# INPUT_AND_OUPUT.net
KiCad netlist of a schematic drawn in Altium Designer
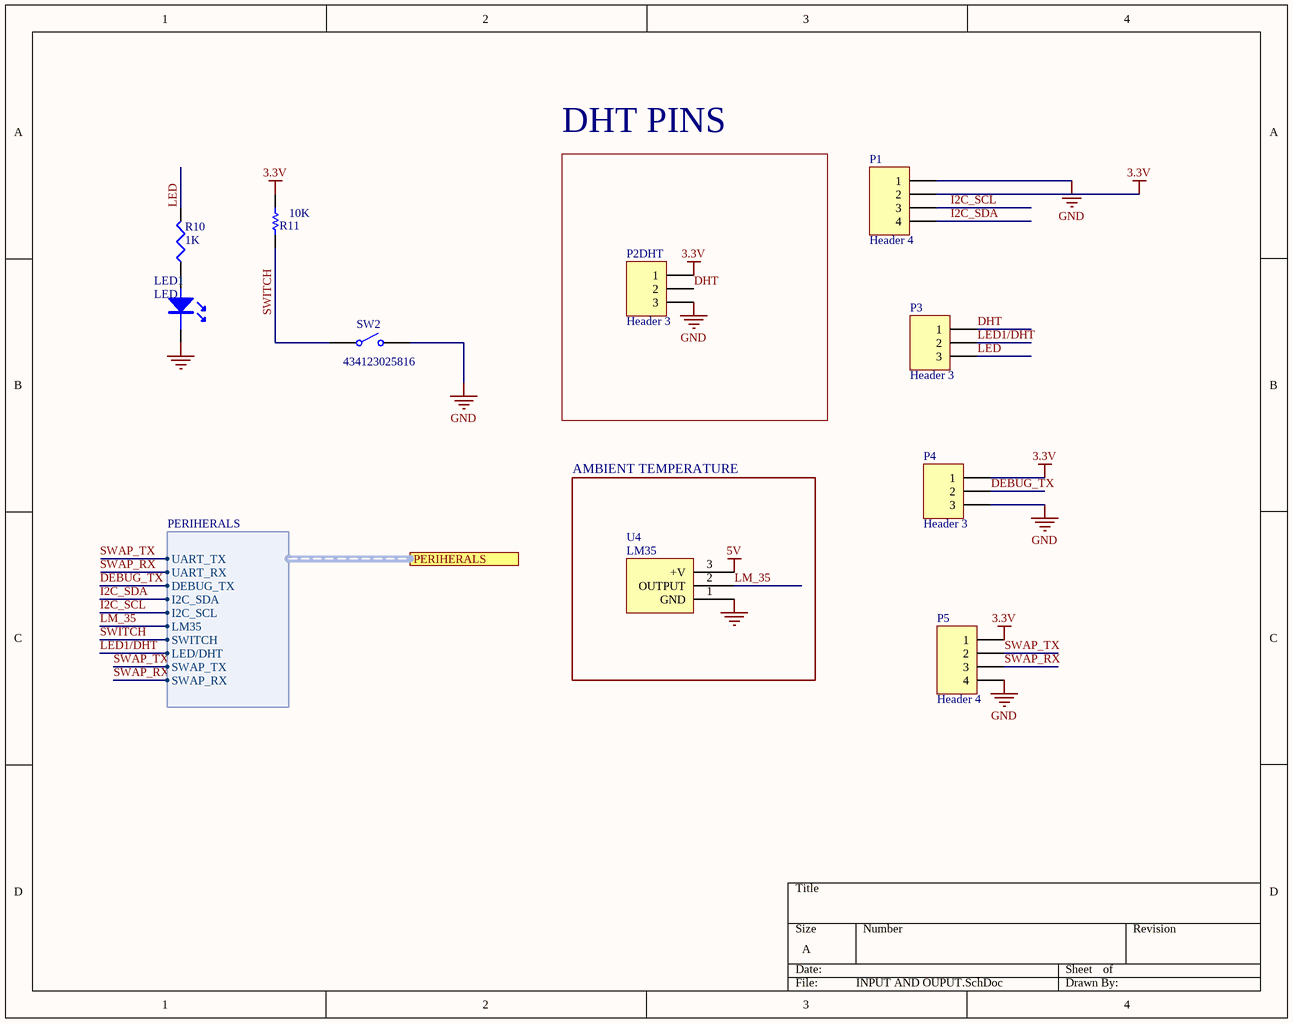
[diagram p0: INPUT AND OUPUT.SchDoc]

(export (version "E")
  (design (tool "Eeschema 10.0.6"))
  (components
    (comp (ref "LED1") (value "LED") (footprint "Type 3mm") (libsource (lib "Devices") (part "LED")))
    (comp (ref "P1")
      (value "Header 4")
      (footprint "HDR1X4")
      (description "Header, 4-Pin")
      (fields (field (name "PUBLISHER") "Altium Limited"))
      (libsource (lib "Miscellaneous Connectors") (part "Header 4"))
    )
    (comp (ref "P2DHT")
      (value "Header 3")
      (footprint "HDR1X3")
      (description "Header, 3-Pin")
      (fields (field (name "PUBLISHER") "Altium Limited"))
      (libsource (lib "Miscellaneous Connectors") (part "Header 3"))
    )
    (comp (ref "P3")
      (value "Header 3")
      (footprint "HDR1X3")
      (description "Header, 3-Pin")
      (fields (field (name "PUBLISHER") "Altium Limited"))
      (libsource (lib "Miscellaneous Connectors") (part "Header 3"))
    )
    (comp (ref "P4")
      (value "Header 3")
      (footprint "HDR1X3")
      (description "Header, 3-Pin")
      (fields (field (name "PUBLISHER") "Altium Limited"))
      (libsource (lib "Miscellaneous Connectors") (part "Header 3"))
    )
    (comp (ref "P5")
      (value "Header 4")
      (footprint "HDR1X4")
      (description "Header, 4-Pin")
      (fields (field (name "PUBLISHER") "Altium Limited"))
      (libsource (lib "Miscellaneous Connectors") (part "Header 4"))
    )
    (comp (ref "R10")
      (value "1K")
      (footprint "RESC0603")
      (description "RESISTOR")
      (libsource (lib "Devices") (part "RES1"))
    )
    (comp (ref "R11")
      (value "10K")
      (footprint "RESC0603")
      (description "2R55 0.125W 1% 0805 (2012 Metric)  SMD")
      (fields (field (name "TOLERANCE") "1 %") (field (name "POWER") "0.125 W"))
      (libsource (lib "Components - 22.01.19 - 11.39") (part "RES"))
    )
    (comp (ref "SW2")
      (value "434123025816")
      (footprint "434123025816")
      (description "WS-TASV J-Bend SMD Tact Switch 6.0X3.8 mm")
      (fields (field (name "MANUFACTURER") "Wuerth Elektronik"))
      (libsource (lib "Altium Content Vault") (part "WE-TACT-SW-2"))
    )
    (comp (ref "U4") (value "LM35") (footprint "TO92S") (libsource (lib "CustomParts") (part "LM35")))
  )
  (nets
    (net (code "2") (name "/DEBUG_TX") (class "Default")
      (node (ref "P4") (pin "2") (pinfunction "2_2") (pintype "passive"))
    )
    (net (code "3") (name "/DHT") (class "Default")
      (node (ref "P2DHT") (pin "2") (pinfunction "2_2") (pintype "passive"))
      (node (ref "P3") (pin "1") (pinfunction "1_1") (pintype "passive"))
    )
    (net (code "4") (name "/I2C_SCL") (class "Default")
      (node (ref "P1") (pin "3") (pinfunction "3_3") (pintype "passive"))
    )
    (net (code "5") (name "/I2C_SDA") (class "Default")
      (node (ref "P1") (pin "4") (pinfunction "4_4") (pintype "passive"))
    )
    (net (code "6") (name "/LED") (class "Default")
      (node (ref "P3") (pin "3") (pinfunction "3_3") (pintype "passive"))
      (node (ref "R10") (pin "2") (pintype "passive"))
    )
    (net (code "7") (name "/LED1{slash}DHT") (class "Default")
      (node (ref "P3") (pin "2") (pinfunction "2_2") (pintype "passive"))
    )
    (net (code "8") (name "/LM_35") (class "Default")
      (node (ref "U4") (pin "2") (pinfunction "OUTPUT_2") (pintype "passive"))
    )
    (net (code "9") (name "/SWAP_RX") (class "Default")
      (node (ref "P5") (pin "3") (pinfunction "3_3") (pintype "passive"))
    )
    (net (code "10") (name "/SWAP_TX") (class "Default")
      (node (ref "P5") (pin "2") (pinfunction "2_2") (pintype "passive"))
    )
    (net (code "11") (name "/SWITCH") (class "Default")
      (node (ref "R11") (pin "1") (pinfunction "1_1") (pintype "passive"))
      (node (ref "SW2") (pin "1") (pinfunction "1_1") (pintype "passive"))
    )
    (net (code "13") (name "3.3V") (class "Default")
      (node (ref "P1") (pin "2") (pinfunction "2_2") (pintype "passive"))
      (node (ref "P2DHT") (pin "1") (pinfunction "1_1") (pintype "passive"))
      (node (ref "P4") (pin "1") (pinfunction "1_1") (pintype "passive"))
      (node (ref "P5") (pin "1") (pinfunction "1_1") (pintype "passive"))
      (node (ref "R11") (pin "2") (pinfunction "2_2") (pintype "passive"))
    )
    (net (code "14") (name "5V") (class "Default")
      (node (ref "U4") (pin "3") (pinfunction "+V_3") (pintype "passive"))
    )
    (net (code "15") (name "GND") (class "Default")
      (node (ref "LED1") (pin "1") (pinfunction "A_1") (pintype "passive"))
      (node (ref "P1") (pin "1") (pinfunction "1_1") (pintype "passive"))
      (node (ref "P2DHT") (pin "3") (pinfunction "3_3") (pintype "passive"))
      (node (ref "P4") (pin "3") (pinfunction "3_3") (pintype "passive"))
      (node (ref "P5") (pin "4") (pinfunction "4_4") (pintype "passive"))
      (node (ref "SW2") (pin "2") (pinfunction "2_2") (pintype "passive"))
      (node (ref "U4") (pin "1") (pinfunction "GND_1") (pintype "passive"))
    )
    (net (code "16") (name "Net-(LED1-K)") (class "Default")
      (node (ref "LED1") (pin "2") (pinfunction "K_2") (pintype "passive"))
      (node (ref "R10") (pin "1") (pintype "passive"))
    )
  )
)
